# Power_supply.net
KiCad netlist of a schematic drawn in Altium Designer
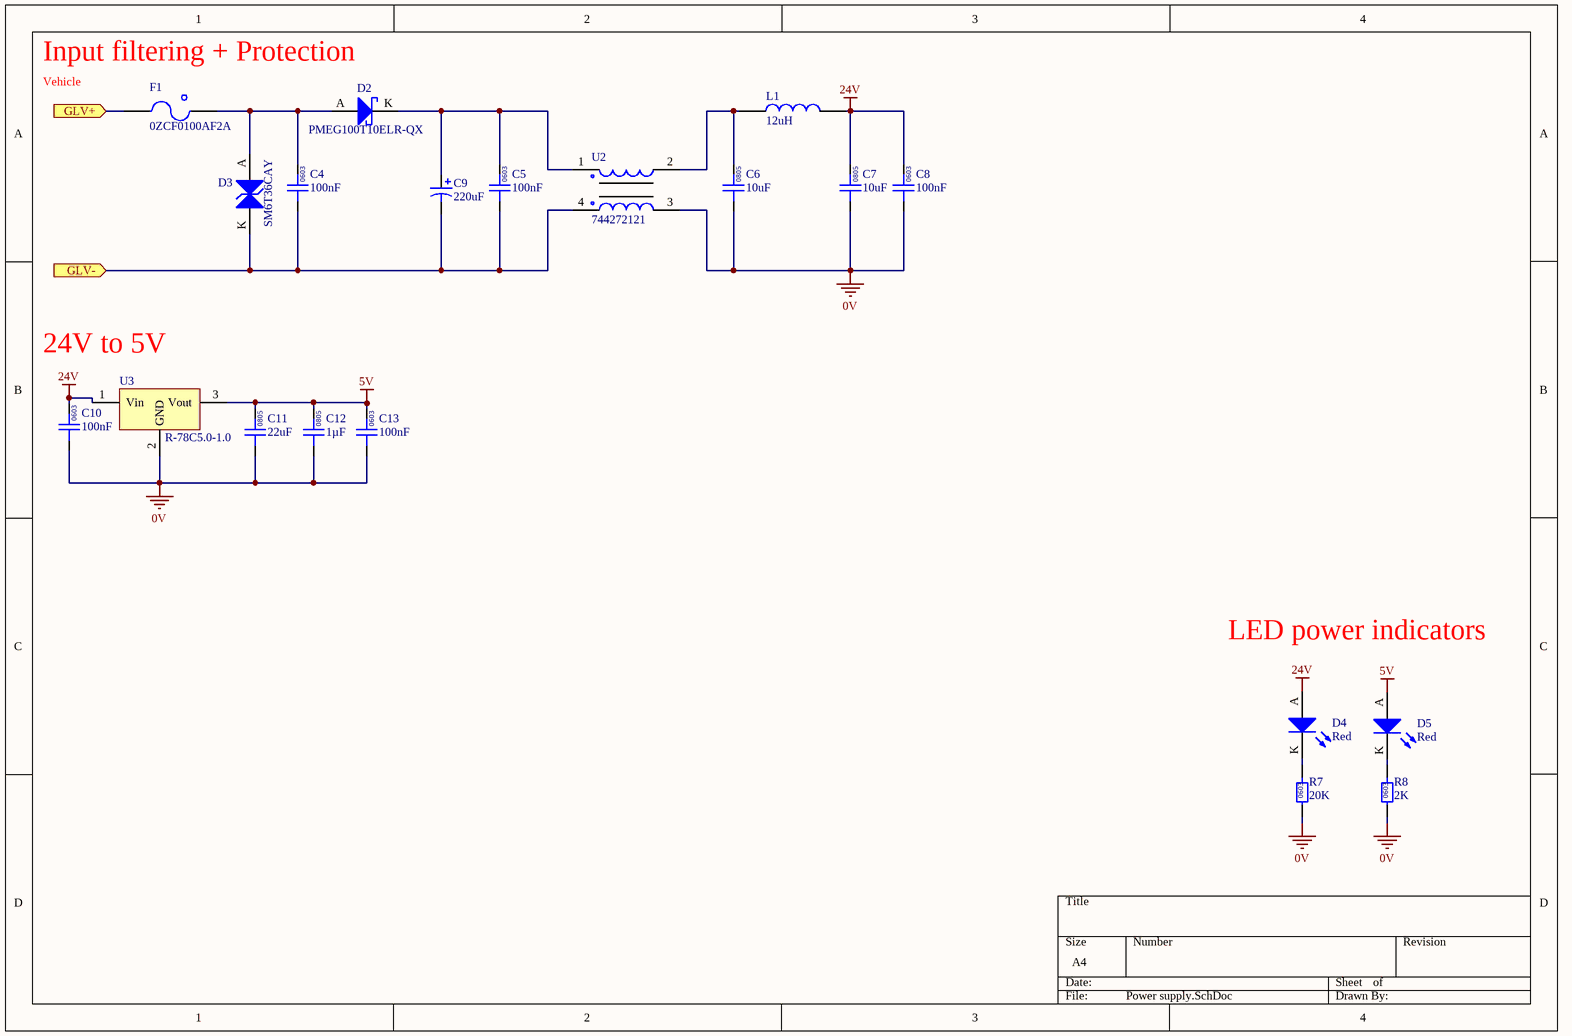
[diagram p0: Power supply.SchDoc]

(export (version "E")
  (design (tool "Eeschema 10.0.6"))
  (components
    (comp (ref "C4")
      (value "100nF")
      (footprint "0603")
      (fields
        (field (name "PART NUMBER") "GCM188L81H104KA57D")
        (field (name "MANUFACTURER") "muRata")
        (field (name "TOLERANCE") "±10%")
      )
      (libsource (lib "ts_standard_library") (part "Capacitor 0603"))
    )
    (comp (ref "C5")
      (value "100nF")
      (footprint "0603")
      (fields
        (field (name "PART NUMBER") "GCM188L81H104KA57D")
        (field (name "MANUFACTURER") "muRata")
        (field (name "TOLERANCE") "±10%")
      )
      (libsource (lib "ts_standard_library") (part "Capacitor 0603"))
    )
    (comp (ref "C6")
      (value "10uF")
      (footprint "0805")
      (fields
        (field (name "PART NUMBER") "GRM21BR6YA106KE43L")
        (field (name "MANUFACTURER") "muRata")
        (field (name "TOLERANCE") "10%")
      )
      (libsource (lib "ts_standard_library") (part "Capacitor 0805"))
    )
    (comp (ref "C7")
      (value "10uF")
      (footprint "0805")
      (fields
        (field (name "PART NUMBER") "GRM21BR6YA106KE43L")
        (field (name "MANUFACTURER") "muRata")
        (field (name "TOLERANCE") "10%")
      )
      (libsource (lib "ts_standard_library") (part "Capacitor 0805"))
    )
    (comp (ref "C8")
      (value "100nF")
      (footprint "0603")
      (fields
        (field (name "PART NUMBER") "GCM188L81H104KA57D")
        (field (name "MANUFACTURER") "muRata")
        (field (name "TOLERANCE") "±10%")
      )
      (libsource (lib "ts_standard_library") (part "Capacitor 0603"))
    )
    (comp (ref "C9")
      (value "220uF")
      (footprint "Vishay Radial 1213")
      (fields
        (field (name "PART NUMBER") "MAL214699106E3")
        (field (name "MANUFACTURER") "Vishay")
        (field (name "TOLERANCE") "20%")
      )
      (libsource (lib "ts_standard_library") (part "Capacitor (Polarised)"))
    )
    (comp (ref "C10")
      (value "100nF")
      (footprint "0603")
      (fields
        (field (name "PART NUMBER") "GCM188L81H104KA57D")
        (field (name "MANUFACTURER") "muRata")
        (field (name "TOLERANCE") "±10%")
      )
      (libsource (lib "ts_standard_library") (part "Capacitor 0603"))
    )
    (comp (ref "C11")
      (value "22uF")
      (footprint "0805")
      (fields
        (field (name "PART NUMBER") "GRM21BR61A226ME51L")
        (field (name "MANUFACTURER") "muRata")
        (field (name "TOLERANCE") "20%")
      )
      (libsource (lib "ts_standard_library") (part "Capacitor 0805"))
    )
    (comp (ref "C12")
      (value "1µF")
      (footprint "0805")
      (fields
        (field (name "PART NUMBER") "GCM21BR71H105KA03L")
        (field (name "MANUFACTURER") "muRata")
        (field (name "TOLERANCE") "±10%")
      )
      (libsource (lib "ts_standard_library") (part "Capacitor 0805"))
    )
    (comp (ref "C13")
      (value "100nF")
      (footprint "0603")
      (fields
        (field (name "PART NUMBER") "GCM188L81H104KA57D")
        (field (name "MANUFACTURER") "muRata")
        (field (name "TOLERANCE") "±10%")
      )
      (libsource (lib "ts_standard_library") (part "Capacitor 0603"))
    )
    (comp (ref "D2")
      (value "PMEG100T10ELR-QX")
      (footprint "NXP SOD123W")
      (fields
        (field (name "MANUFACTURER") "Nexperia USA Inc.")
        (field (name "DIGIKEY PART NUMBER") "1727-PMEG100T10ELR-QXCT-ND")
      )
      (libsource (lib "ts_standard_library") (part "Diode (Schottky)"))
    )
    (comp (ref "D3")
      (value "SM6T36CAY")
      (footprint "ST SMB DIODE")
      (fields
        (field (name "MANUFACTURER") "STMicroelectronics")
        (field (name "DIGIKEY PART NUMBER") "497-10804-1-ND")
      )
      (libsource (lib "ts_standard_library") (part "TVS (Bidirectional)"))
    )
    (comp (ref "D4")
      (value "Red")
      (footprint "0805 LED")
      (description "Red LED Indication - Discrete 1.75V 0805 (2012 Metric)")
      (fields (field (name "PART NUMBER") "SML-210LTT86") (field (name "MANUFACTURER") "ROHM Semiconductor"))
      (libsource (lib "ts_standard_library") (part "LED"))
    )
    (comp (ref "D5")
      (value "Red")
      (footprint "0805 LED")
      (description "Red LED Indication - Discrete 1.75V 0805 (2012 Metric)")
      (fields (field (name "PART NUMBER") "SML-210LTT86") (field (name "MANUFACTURER") "ROHM Semiconductor"))
      (libsource (lib "ts_standard_library") (part "LED"))
    )
    (comp (ref "F1")
      (value "0ZCF0100AF2A")
      (footprint "2920")
      (description "PTC RESET FUSE 60V 1A 292")
      (fields
        (field (name "MANUFACTURER") "Littelfuse Inc.")
        (field (name "DIGIKEY PART NUMBER") "507-2070-1-ND")
      )
      (libsource (lib "ts_standard_library") (part "PTC Fuse"))
    )
    (comp (ref "L1")
      (value "12uH")
      (footprint "1812")
      (fields
        (field (name "PART NUMBER") "RLS-126")
        (field (name "MANUFACTURER") "Recom")
        (field (name "TOLERANCE") "0.2")
      )
      (libsource (lib "ts_standard_library") (part "Inductor"))
    )
    (comp (ref "R7")
      (value "20K")
      (footprint "0603")
      (fields
        (field (name "PART NUMBER") "RC0603FR-0720KL")
        (field (name "MANUFACTURER") "YAGEO")
        (field (name "TOLERANCE") "0.01")
      )
      (libsource (lib "ts_standard_library") (part "Resistor 0603"))
    )
    (comp (ref "R8")
      (value "2K")
      (footprint "0603")
      (fields
        (field (name "PART NUMBER") "RC0603FR-072KL")
        (field (name "MANUFACTURER") "YAGEO")
        (field (name "TOLERANCE") "0.01")
      )
      (libsource (lib "ts_standard_library") (part "Resistor 0603"))
    )
    (comp (ref "U2")
      (value "744272121")
      (footprint "Wurth 4-PC Pad")
      (fields
        (field (name "MANUFACTURER") "Wurth Electronics Inc")
        (field (name "DIGIKEY PART NUMBER") "732-1489-1-ND")
      )
      (libsource (lib "ts_standard_library") (part "CM Choke"))
    )
    (comp (ref "U3")
      (value "R-78C5.0-1.0")
      (footprint "RECOM 3-SIP")
      (description "CONV DC/DC 1A 5V OUT SIP VERT")
      (fields (field (name "MANUFACTURER") "Recom") (field (name "DIGIKEY PART NUMBER") "945-1395-5-ND"))
      (libsource (lib "ts_standard_library") (part "R-78C5.0-1.0"))
    )
  )
  (nets
    (net (code "1") (name "/GLV+") (class "Default")
      (node (ref "F1") (pin "1") (pinfunction "1_1") (pintype "passive"))
    )
    (net (code "2") (name "/GLV-") (class "Default")
      (node (ref "C4") (pin "1") (pinfunction "1_1") (pintype "passive"))
      (node (ref "C5") (pin "1") (pinfunction "1_1") (pintype "passive"))
      (node (ref "C9") (pin "1") (pinfunction "1_1") (pintype "passive"))
      (node (ref "D3") (pin "K") (pinfunction "K_K") (pintype "passive"))
      (node (ref "U2") (pin "4") (pinfunction "4_4") (pintype "passive"))
    )
    (net (code "3") (name "0V") (class "Default")
      (node (ref "C10") (pin "1") (pinfunction "1_1") (pintype "passive"))
      (node (ref "C11") (pin "1") (pinfunction "1_1") (pintype "passive"))
      (node (ref "C12") (pin "1") (pinfunction "1_1") (pintype "passive"))
      (node (ref "C13") (pin "1") (pinfunction "1_1") (pintype "passive"))
      (node (ref "C6") (pin "1") (pinfunction "1_1") (pintype "passive"))
      (node (ref "C7") (pin "1") (pinfunction "1_1") (pintype "passive"))
      (node (ref "C8") (pin "1") (pinfunction "1_1") (pintype "passive"))
      (node (ref "R7") (pin "1") (pinfunction "1_1") (pintype "passive"))
      (node (ref "R8") (pin "1") (pinfunction "1_1") (pintype "passive"))
      (node (ref "U2") (pin "3") (pinfunction "3_3") (pintype "power_in"))
      (node (ref "U3") (pin "2") (pinfunction "GND_2") (pintype "passive"))
    )
    (net (code "4") (name "5V") (class "Default")
      (node (ref "C11") (pin "2") (pinfunction "2_2") (pintype "passive"))
      (node (ref "C12") (pin "2") (pinfunction "2_2") (pintype "passive"))
      (node (ref "C13") (pin "2") (pinfunction "2_2") (pintype "passive"))
      (node (ref "D5") (pin "A") (pinfunction "A_A") (pintype "passive"))
      (node (ref "U3") (pin "3") (pinfunction "Vout_3") (pintype "passive"))
    )
    (net (code "5") (name "24V") (class "Default")
      (node (ref "C10") (pin "2") (pinfunction "2_2") (pintype "passive"))
      (node (ref "C7") (pin "2") (pinfunction "2_2") (pintype "passive"))
      (node (ref "C8") (pin "2") (pinfunction "2_2") (pintype "passive"))
      (node (ref "D4") (pin "A") (pinfunction "A_A") (pintype "passive"))
      (node (ref "L1") (pin "1") (pinfunction "1_1") (pintype "passive"))
      (node (ref "U3") (pin "1") (pinfunction "Vin_1") (pintype "passive"))
    )
    (net (code "6") (name "Net-(C4-Pad2)") (class "Default")
      (node (ref "C4") (pin "2") (pinfunction "2_2") (pintype "passive"))
      (node (ref "D2") (pin "A") (pinfunction "A_A") (pintype "passive"))
      (node (ref "D3") (pin "A") (pinfunction "A_A") (pintype "passive"))
      (node (ref "F1") (pin "2") (pinfunction "2_2") (pintype "passive"))
    )
    (net (code "7") (name "Net-(C5-Pad2)") (class "Default")
      (node (ref "C5") (pin "2") (pinfunction "2_2") (pintype "passive"))
      (node (ref "C9") (pin "2") (pinfunction "2_2") (pintype "passive"))
      (node (ref "D2") (pin "K") (pinfunction "K_K") (pintype "passive"))
      (node (ref "U2") (pin "1") (pinfunction "1_1") (pintype "passive"))
    )
    (net (code "8") (name "Net-(C6-Pad2)") (class "Default")
      (node (ref "C6") (pin "2") (pinfunction "2_2") (pintype "passive"))
      (node (ref "L1") (pin "2") (pinfunction "2_2") (pintype "passive"))
      (node (ref "U2") (pin "2") (pinfunction "2_2") (pintype "passive"))
    )
    (net (code "9") (name "Net-(D4-PadK)") (class "Default")
      (node (ref "D4") (pin "K") (pinfunction "K_K") (pintype "passive"))
      (node (ref "R7") (pin "2") (pinfunction "2_2") (pintype "passive"))
    )
    (net (code "10") (name "Net-(D5-PadK)") (class "Default")
      (node (ref "D5") (pin "K") (pinfunction "K_K") (pintype "passive"))
      (node (ref "R8") (pin "2") (pinfunction "2_2") (pintype "passive"))
    )
  )
)
